# slipsensor_v2.net
KiCad netlist of a schematic drawn in EAGLE
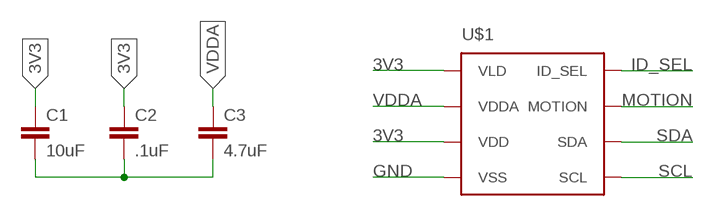
[diagram p0: schematic, sheet 1]

(export (version "E")
  (design (tool "Eeschema 10.0.6"))
  (components
    (comp (ref "C1")
      (value "10uF")
      (footprint "eagle-import:C0402")
      (libsource (lib "eagle-import") (part "C-EUC0402"))
    )
    (comp (ref "C2")
      (value ".1uF")
      (footprint "eagle-import:C0402")
      (libsource (lib "eagle-import") (part "C-EUC0402"))
    )
    (comp (ref "C3")
      (value "4.7uF")
      (footprint "eagle-import:C0402")
      (libsource (lib "eagle-import") (part "C-EUC0402"))
    )
    (comp (ref "U$1")
      (value "PAT9125EL")
      (footprint "eagle-import:PAT9125EL")
      (libsource (lib "eagle-import") (part "PAT9125EL"))
    )
  )
  (nets
    (net (code "1") (name "/GND") (class "Default")
      (node (ref "C1") (pin "2") (pinfunction "2_2") (pintype "passive"))
      (node (ref "C2") (pin "2") (pinfunction "2_2") (pintype "passive"))
      (node (ref "C3") (pin "2") (pinfunction "2_2") (pintype "passive"))
      (node (ref "U$1") (pin "P$4") (pinfunction "VSS_P$4") (pintype "bidirectional"))
    )
    (net (code "2") (name "/ID_SEL") (class "Default")
      (node (ref "U$1") (pin "P$8") (pinfunction "ID_SEL_P$8") (pintype "input"))
    )
    (net (code "3") (name "/MOTION") (class "Default")
      (node (ref "U$1") (pin "P$7") (pinfunction "MOTION_P$7") (pintype "input"))
    )
    (net (code "4") (name "/SCL") (class "Default")
      (node (ref "U$1") (pin "P$5") (pinfunction "SCL_P$5") (pintype "input"))
    )
    (net (code "5") (name "/SDA") (class "Default")
      (node (ref "U$1") (pin "P$6") (pinfunction "SDA_P$6") (pintype "input"))
    )
    (net (code "6") (name "3V3") (class "Default")
      (node (ref "C1") (pin "1") (pinfunction "1_1") (pintype "passive"))
      (node (ref "C2") (pin "1") (pinfunction "1_1") (pintype "passive"))
      (node (ref "U$1") (pin "P$1") (pinfunction "VLD_P$1") (pintype "bidirectional"))
      (node (ref "U$1") (pin "P$3") (pinfunction "VDD_P$3") (pintype "bidirectional"))
    )
    (net (code "7") (name "VDDA") (class "Default")
      (node (ref "C3") (pin "1") (pinfunction "1_1") (pintype "passive"))
      (node (ref "U$1") (pin "P$2") (pinfunction "VDDA_P$2") (pintype "bidirectional"))
    )
  )
)
